# E17-04-HV-CONNECTORS.net
KiCad netlist of a schematic drawn in Altium Designer
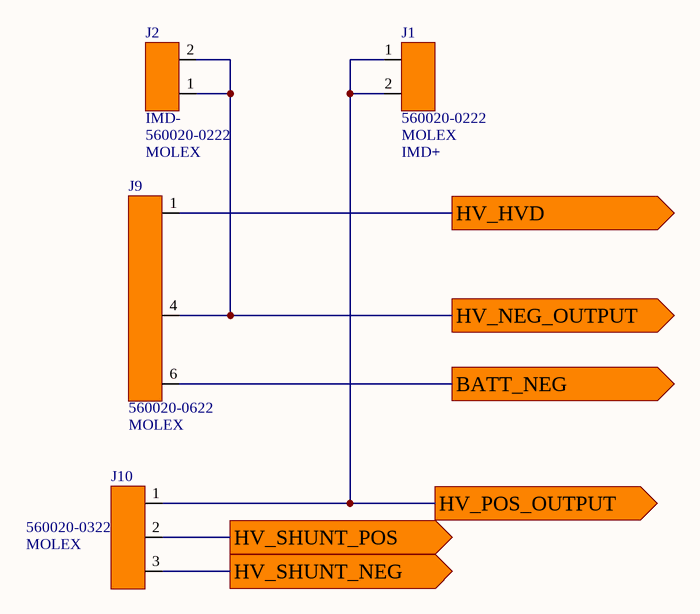
[diagram p0: E17-04-HV-CONNECTORS.SchDoc]

(export (version "E")
  (design (tool "Eeschema 10.0.6"))
  (components
    (comp (ref "J1")
      (value "IMD+")
      (footprint "MOLEX_DURACLIK_2 RED VERT")
      (description "MOLEX DURACLIK 2-PIN VERT RED")
      (fields
        (field (name "VOLTAGE") "125")
        (field (name "MPN") "560020-0222")
        (field (name "MANUFACTURER") "MOLEX")
      )
      (libsource (lib "Molex_DuraClik") (part "560020-0222"))
    )
    (comp (ref "J2")
      (value "IMD-")
      (footprint "MOLEX_DURACLIK_2 RED VERT")
      (description "MOLEX DURACLIK 2-PIN VERT RED")
      (fields
        (field (name "VOLTAGE") "125")
        (field (name "MPN") "560020-0222")
        (field (name "MANUFACTURER") "MOLEX")
      )
      (libsource (lib "") (part "560020-0222_1"))
    )
    (comp (ref "J9")
      (value "HV BUS")
      (footprint "MOLEX_DURACLIK_6 RED VERT HV")
      (description "MOLEX DURACLIK 6-PIN VERT RED")
      (fields
        (field (name "VOLTAGE") "250")
        (field (name "MPN") "560020-0622")
        (field (name "MANUFACTURER") "MOLEX")
      )
      (libsource (lib "MolexDuraclik") (part "560020-0622_HV"))
    )
    (comp (ref "J10")
      (value "SHUNT")
      (footprint "MOLEX_DURACLIK_3 RED - VERT")
      (description "MOLEX DURACLIK 3-PIN VERT RED")
      (fields
        (field (name "VOLTAGE") "125")
        (field (name "MPN") "560020-0322")
        (field (name "MANUFACTURER") "MOLEX")
      )
      (libsource (lib "Molex_DuraClik") (part "560020-0322"))
    )
  )
  (nets
    (net (code "1") (name "/BATT_NEG") (class "Default")
      (node (ref "J9") (pin "6") (pinfunction "6_6") (pintype "passive"))
    )
    (net (code "2") (name "/HV_HVD") (class "Default")
      (node (ref "J9") (pin "1") (pinfunction "1_1") (pintype "passive"))
    )
    (net (code "3") (name "/HV_NEG_OUTPUT") (class "Default")
      (node (ref "J2") (pin "1") (pinfunction "1_1") (pintype "passive"))
      (node (ref "J2") (pin "2") (pinfunction "2_2") (pintype "passive"))
      (node (ref "J9") (pin "4") (pinfunction "4_4") (pintype "passive"))
    )
    (net (code "4") (name "/HV_POS_OUTPUT") (class "Default")
      (node (ref "J1") (pin "1") (pinfunction "1_1") (pintype "passive"))
      (node (ref "J1") (pin "2") (pinfunction "2_2") (pintype "passive"))
      (node (ref "J10") (pin "1") (pinfunction "1_1") (pintype "passive"))
    )
    (net (code "5") (name "/HV_SHUNT_NEG") (class "Default")
      (node (ref "J10") (pin "3") (pinfunction "3_3") (pintype "passive"))
    )
    (net (code "6") (name "/HV_SHUNT_POS") (class "Default")
      (node (ref "J10") (pin "2") (pinfunction "2_2") (pintype "passive"))
    )
  )
)
